# LAN9303_Nucleo144_Shield.net
KiCad netlist of a schematic drawn in EAGLE
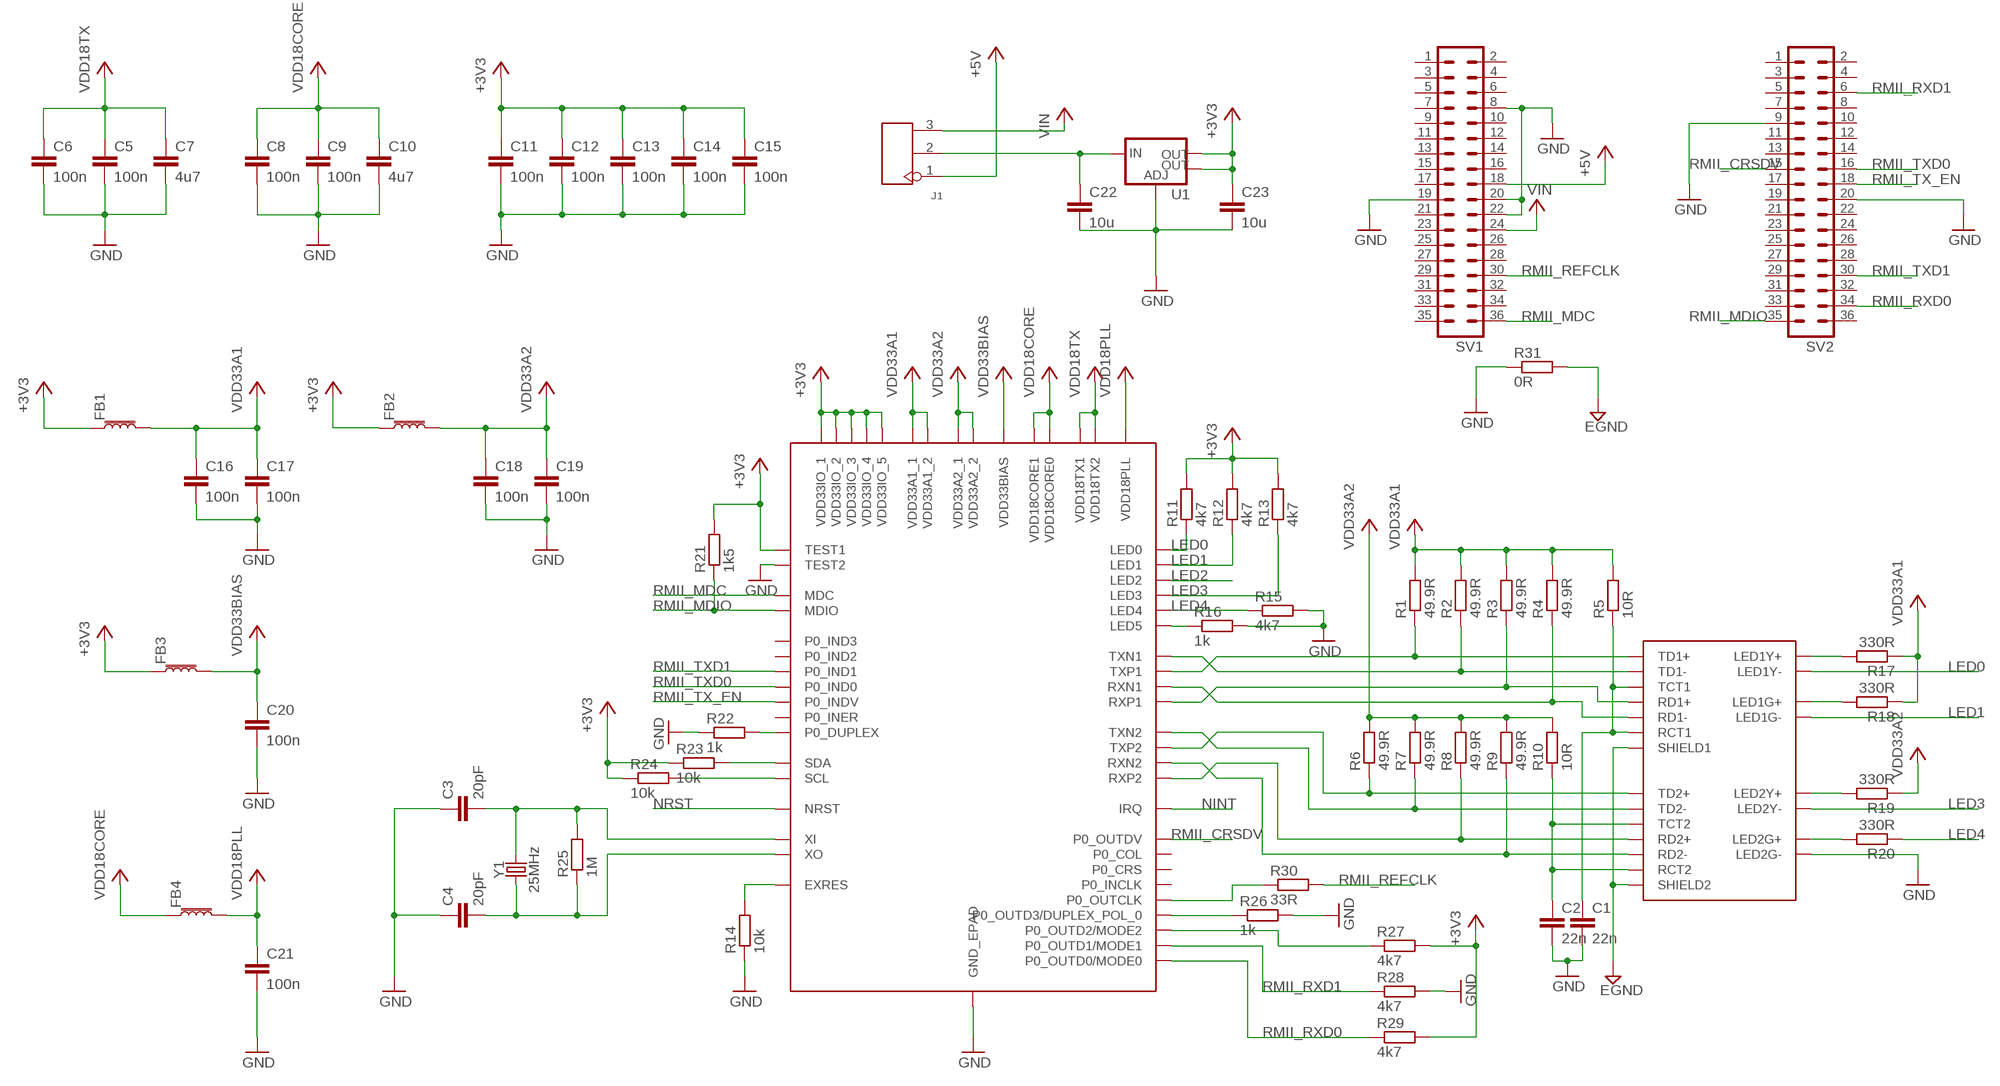
[diagram p0: schematic, sheet 1]

(export (version "E")
  (design (tool "Eeschema 10.0.6"))
  (components
    (comp (ref "C1")
      (value "22n")
      (footprint "eagle-import:C0603")
      (libsource (lib "eagle-import") (part "C-EUC0603"))
    )
    (comp (ref "C2")
      (value "22n")
      (footprint "eagle-import:C0603")
      (libsource (lib "eagle-import") (part "C-EUC0603"))
    )
    (comp (ref "C3")
      (value "20pF")
      (footprint "eagle-import:C0603")
      (libsource (lib "eagle-import") (part "C-EUC0603"))
    )
    (comp (ref "C4")
      (value "20pF")
      (footprint "eagle-import:C0603")
      (libsource (lib "eagle-import") (part "C-EUC0603"))
    )
    (comp (ref "C5")
      (value "100n")
      (footprint "eagle-import:C0603")
      (libsource (lib "eagle-import") (part "C-EUC0603"))
    )
    (comp (ref "C6")
      (value "100n")
      (footprint "eagle-import:C0603")
      (libsource (lib "eagle-import") (part "C-EUC0603"))
    )
    (comp (ref "C7")
      (value "4u7")
      (footprint "eagle-import:C0603")
      (libsource (lib "eagle-import") (part "C-EUC0603"))
    )
    (comp (ref "C8")
      (value "100n")
      (footprint "eagle-import:C0603")
      (libsource (lib "eagle-import") (part "C-EUC0603"))
    )
    (comp (ref "C9")
      (value "100n")
      (footprint "eagle-import:C0603")
      (libsource (lib "eagle-import") (part "C-EUC0603"))
    )
    (comp (ref "C10")
      (value "4u7")
      (footprint "eagle-import:C0603")
      (libsource (lib "eagle-import") (part "C-EUC0603"))
    )
    (comp (ref "C11")
      (value "100n")
      (footprint "eagle-import:C0603")
      (libsource (lib "eagle-import") (part "C-EUC0603"))
    )
    (comp (ref "C12")
      (value "100n")
      (footprint "eagle-import:C0603")
      (libsource (lib "eagle-import") (part "C-EUC0603"))
    )
    (comp (ref "C13")
      (value "100n")
      (footprint "eagle-import:C0603")
      (libsource (lib "eagle-import") (part "C-EUC0603"))
    )
    (comp (ref "C14")
      (value "100n")
      (footprint "eagle-import:C0603")
      (libsource (lib "eagle-import") (part "C-EUC0603"))
    )
    (comp (ref "C15")
      (value "100n")
      (footprint "eagle-import:C0603")
      (libsource (lib "eagle-import") (part "C-EUC0603"))
    )
    (comp (ref "C16")
      (value "100n")
      (footprint "eagle-import:C0603")
      (libsource (lib "eagle-import") (part "C-EUC0603"))
    )
    (comp (ref "C17")
      (value "100n")
      (footprint "eagle-import:C0603")
      (libsource (lib "eagle-import") (part "C-EUC0603"))
    )
    (comp (ref "C18")
      (value "100n")
      (footprint "eagle-import:C0603")
      (libsource (lib "eagle-import") (part "C-EUC0603"))
    )
    (comp (ref "C19")
      (value "100n")
      (footprint "eagle-import:C0603")
      (libsource (lib "eagle-import") (part "C-EUC0603"))
    )
    (comp (ref "C20")
      (value "100n")
      (footprint "eagle-import:C0603")
      (libsource (lib "eagle-import") (part "C-EUC0603"))
    )
    (comp (ref "C21")
      (value "100n")
      (footprint "eagle-import:C0603")
      (libsource (lib "eagle-import") (part "C-EUC0603"))
    )
    (comp (ref "C22")
      (value "10u")
      (footprint "eagle-import:C1206")
      (libsource (lib "eagle-import") (part "C-EUC1206"))
    )
    (comp (ref "C23")
      (value "10u")
      (footprint "eagle-import:C1206")
      (libsource (lib "eagle-import") (part "C-EUC1206"))
    )
    (comp (ref "FB1")
      (value "FERRITE_BEAD-0603")
      (footprint "eagle-import:0603")
      (libsource (lib "eagle-import") (part "FERRITE_BEAD-0603"))
    )
    (comp (ref "FB2")
      (value "FERRITE_BEAD-0603")
      (footprint "eagle-import:0603")
      (libsource (lib "eagle-import") (part "FERRITE_BEAD-0603"))
    )
    (comp (ref "FB3")
      (value "FERRITE_BEAD-0603")
      (footprint "eagle-import:0603")
      (libsource (lib "eagle-import") (part "FERRITE_BEAD-0603"))
    )
    (comp (ref "FB4")
      (value "FERRITE_BEAD-0603")
      (footprint "eagle-import:0603")
      (libsource (lib "eagle-import") (part "FERRITE_BEAD-0603"))
    )
    (comp (ref "J1")
      (value "DIP-BLACK-FEMALE-HEADER-VERT(3P-2.54)")
      (footprint "eagle-import:H3-2.54")
      (fields (field (name "MPN") "F185-1103A0BSYA1"))
      (libsource (lib "eagle-import") (part "DIP-BLACK-FEMALE-HEADER-VERT(3P-2.54)"))
    )
    (comp (ref "R1")
      (value "49.9R")
      (footprint "eagle-import:R0603")
      (libsource (lib "eagle-import") (part "R-EU_R0603"))
    )
    (comp (ref "R2")
      (value "49.9R")
      (footprint "eagle-import:R0603")
      (libsource (lib "eagle-import") (part "R-EU_R0603"))
    )
    (comp (ref "R3")
      (value "49.9R")
      (footprint "eagle-import:R0603")
      (libsource (lib "eagle-import") (part "R-EU_R0603"))
    )
    (comp (ref "R4")
      (value "49.9R")
      (footprint "eagle-import:R0603")
      (libsource (lib "eagle-import") (part "R-EU_R0603"))
    )
    (comp (ref "R5")
      (value "10R")
      (footprint "eagle-import:R0603")
      (libsource (lib "eagle-import") (part "R-EU_R0603"))
    )
    (comp (ref "R6")
      (value "49.9R")
      (footprint "eagle-import:R0603")
      (libsource (lib "eagle-import") (part "R-EU_R0603"))
    )
    (comp (ref "R7")
      (value "49.9R")
      (footprint "eagle-import:R0603")
      (libsource (lib "eagle-import") (part "R-EU_R0603"))
    )
    (comp (ref "R8")
      (value "49.9R")
      (footprint "eagle-import:R0603")
      (libsource (lib "eagle-import") (part "R-EU_R0603"))
    )
    (comp (ref "R9")
      (value "49.9R")
      (footprint "eagle-import:R0603")
      (libsource (lib "eagle-import") (part "R-EU_R0603"))
    )
    (comp (ref "R10")
      (value "10R")
      (footprint "eagle-import:R0603")
      (libsource (lib "eagle-import") (part "R-EU_R0603"))
    )
    (comp (ref "R11")
      (value "4k7")
      (footprint "eagle-import:R0603")
      (libsource (lib "eagle-import") (part "R-EU_R0603"))
    )
    (comp (ref "R12")
      (value "4k7")
      (footprint "eagle-import:R0603")
      (libsource (lib "eagle-import") (part "R-EU_R0603"))
    )
    (comp (ref "R13")
      (value "4k7")
      (footprint "eagle-import:R0603")
      (libsource (lib "eagle-import") (part "R-EU_R0603"))
    )
    (comp (ref "R14")
      (value "10k")
      (footprint "eagle-import:R0603")
      (libsource (lib "eagle-import") (part "R-EU_R0603"))
    )
    (comp (ref "R15")
      (value "4k7")
      (footprint "eagle-import:R0603")
      (libsource (lib "eagle-import") (part "R-EU_R0603"))
    )
    (comp (ref "R16")
      (value "1k")
      (footprint "eagle-import:R0603")
      (libsource (lib "eagle-import") (part "R-EU_R0603"))
    )
    (comp (ref "R17")
      (value "330R")
      (footprint "eagle-import:R0603")
      (libsource (lib "eagle-import") (part "R-EU_R0603"))
    )
    (comp (ref "R18")
      (value "330R")
      (footprint "eagle-import:R0603")
      (libsource (lib "eagle-import") (part "R-EU_R0603"))
    )
    (comp (ref "R19")
      (value "330R")
      (footprint "eagle-import:R0603")
      (libsource (lib "eagle-import") (part "R-EU_R0603"))
    )
    (comp (ref "R20")
      (value "330R")
      (footprint "eagle-import:R0603")
      (libsource (lib "eagle-import") (part "R-EU_R0603"))
    )
    (comp (ref "R21")
      (value "1k5")
      (footprint "eagle-import:R0603")
      (libsource (lib "eagle-import") (part "R-EU_R0603"))
    )
    (comp (ref "R22")
      (value "1k")
      (footprint "eagle-import:R0603")
      (libsource (lib "eagle-import") (part "R-EU_R0603"))
    )
    (comp (ref "R23")
      (value "10k")
      (footprint "eagle-import:R0603")
      (libsource (lib "eagle-import") (part "R-EU_R0603"))
    )
    (comp (ref "R24")
      (value "10k")
      (footprint "eagle-import:R0603")
      (libsource (lib "eagle-import") (part "R-EU_R0603"))
    )
    (comp (ref "R25")
      (value "1M")
      (footprint "eagle-import:R0603")
      (libsource (lib "eagle-import") (part "R-EU_R0603"))
    )
    (comp (ref "R26")
      (value "1k")
      (footprint "eagle-import:R0603")
      (libsource (lib "eagle-import") (part "R-EU_R0603"))
    )
    (comp (ref "R27")
      (value "4k7")
      (footprint "eagle-import:R0603")
      (libsource (lib "eagle-import") (part "R-EU_R0603"))
    )
    (comp (ref "R28")
      (value "4k7")
      (footprint "eagle-import:R0603")
      (libsource (lib "eagle-import") (part "R-EU_R0603"))
    )
    (comp (ref "R29")
      (value "4k7")
      (footprint "eagle-import:R0603")
      (libsource (lib "eagle-import") (part "R-EU_R0603"))
    )
    (comp (ref "R30")
      (value "33R")
      (footprint "eagle-import:R0603")
      (libsource (lib "eagle-import") (part "R-EU_R0603"))
    )
    (comp (ref "R31")
      (value "0R")
      (footprint "eagle-import:R0805")
      (libsource (lib "eagle-import") (part "R-EU_R0805"))
    )
    (comp (ref "SV1")
      (value "MA18-2")
      (footprint "eagle-import:MA18-2")
      (libsource (lib "eagle-import") (part "MA18-2"))
    )
    (comp (ref "SV2")
      (value "MA18-2")
      (footprint "eagle-import:MA18-2")
      (libsource (lib "eagle-import") (part "MA18-2"))
    )
    (comp (ref "U$1")
      (value "LAN9303")
      (footprint "eagle-import:QFN56")
      (libsource (lib "eagle-import") (part "LAN9303_ABZJ"))
    )
    (comp (ref "U$2")
      (value "WE_DUAL_RJ45JACK")
      (footprint "eagle-import:DUAL_RJ45")
      (libsource (lib "eagle-import") (part "WE_DUAL_RJ45JACK"))
    )
    (comp (ref "U1")
      (value "V_REG_LM1117SOT223")
      (footprint "eagle-import:SOT223")
      (libsource (lib "eagle-import") (part "V_REG_LM1117SOT223"))
    )
    (comp (ref "Y1")
      (value "25MHz")
      (footprint "eagle-import:CRYSTAL-SMD-5X3.2-2PAD")
      (libsource (lib "eagle-import") (part "CRYSTALSMD-5X3.2-2PAD"))
    )
  )
  (nets
    (net (code "1") (name "+3V3") (class "Default")
      (node (ref "C11") (pin "1") (pinfunction "1_1") (pintype "passive"))
      (node (ref "C12") (pin "1") (pinfunction "1_1") (pintype "passive"))
      (node (ref "C13") (pin "1") (pinfunction "1_1") (pintype "passive"))
      (node (ref "C14") (pin "1") (pinfunction "1_1") (pintype "passive"))
      (node (ref "C15") (pin "1") (pinfunction "1_1") (pintype "passive"))
      (node (ref "C23") (pin "1") (pinfunction "1_1") (pintype "passive"))
      (node (ref "FB1") (pin "1") (pinfunction "1_1") (pintype "passive"))
      (node (ref "FB2") (pin "1") (pinfunction "1_1") (pintype "passive"))
      (node (ref "FB3") (pin "1") (pinfunction "1_1") (pintype "passive"))
      (node (ref "R11") (pin "2") (pinfunction "2_2") (pintype "passive"))
      (node (ref "R12") (pin "2") (pinfunction "2_2") (pintype "passive"))
      (node (ref "R13") (pin "2") (pinfunction "2_2") (pintype "passive"))
      (node (ref "R21") (pin "2") (pinfunction "2_2") (pintype "passive"))
      (node (ref "R23") (pin "1") (pinfunction "1_1") (pintype "passive"))
      (node (ref "R24") (pin "1") (pinfunction "1_1") (pintype "passive"))
      (node (ref "R27") (pin "2") (pinfunction "2_2") (pintype "passive"))
      (node (ref "R29") (pin "2") (pinfunction "2_2") (pintype "passive"))
      (node (ref "U$1") (pin "15") (pinfunction "VDD33IO_2_15") (pintype "bidirectional"))
      (node (ref "U$1") (pin "23") (pinfunction "VDD33IO_3_23") (pintype "bidirectional"))
      (node (ref "U$1") (pin "30") (pinfunction "VDD33IO_4_30") (pintype "bidirectional"))
      (node (ref "U$1") (pin "32") (pinfunction "VDD33IO_5_32") (pintype "bidirectional"))
      (node (ref "U$1") (pin "33") (pinfunction "TEST1_33") (pintype "bidirectional"))
      (node (ref "U$1") (pin "9") (pinfunction "VDD33IO_1_9") (pintype "bidirectional"))
      (node (ref "U1") (pin "2") (pinfunction "OUT_2") (pintype "output"))
      (node (ref "U1") (pin "4") (pinfunction "OUT_4") (pintype "output"))
    )
    (net (code "2") (name "+5V") (class "Default")
      (node (ref "J1") (pin "1") (pinfunction "P$1_1") (pintype "bidirectional"))
      (node (ref "SV1") (pin "18") (pinfunction "18_18") (pintype "passive"))
    )
    (net (code "3") (name "/LED0") (class "Default")
      (node (ref "R11") (pin "1") (pinfunction "1_1") (pintype "passive"))
      (node (ref "U$1") (pin "29") (pinfunction "LED0_29") (pintype "bidirectional"))
      (node (ref "U$2") (pin "P$1_10") (pinfunction "LED1Y-_P$1_10") (pintype "bidirectional"))
    )
    (net (code "4") (name "/LED1") (class "Default")
      (node (ref "R12") (pin "1") (pinfunction "1_1") (pintype "passive"))
      (node (ref "U$1") (pin "28") (pinfunction "LED1_28") (pintype "bidirectional"))
      (node (ref "U$2") (pin "P$1_12") (pinfunction "LED1G-_P$1_12") (pintype "bidirectional"))
    )
    (net (code "5") (name "/LED2") (class "Default")
      (node (ref "U$1") (pin "27") (pinfunction "LED2_27") (pintype "bidirectional"))
    )
    (net (code "6") (name "/LED3") (class "Default")
      (node (ref "R13") (pin "1") (pinfunction "1_1") (pintype "passive"))
      (node (ref "U$1") (pin "26") (pinfunction "LED3_26") (pintype "bidirectional"))
      (node (ref "U$2") (pin "P$2_10") (pinfunction "LED2Y-_P$2_10") (pintype "bidirectional"))
    )
    (net (code "7") (name "/LED4") (class "Default")
      (node (ref "R15") (pin "1") (pinfunction "1_1") (pintype "passive"))
      (node (ref "R20") (pin "1") (pinfunction "1_1") (pintype "passive"))
      (node (ref "U$1") (pin "25") (pinfunction "LED4_25") (pintype "bidirectional"))
    )
    (net (code "8") (name "/NINT") (class "Default")
      (node (ref "U$1") (pin "38") (pinfunction "IRQ_38") (pintype "bidirectional"))
    )
    (net (code "9") (name "/NRST") (class "Default")
      (node (ref "U$1") (pin "37") (pinfunction "NRST_37") (pintype "bidirectional"))
    )
    (net (code "10") (name "/RMII_CRSDV") (class "Default")
      (node (ref "SV2") (pin "15") (pinfunction "15_15") (pintype "passive"))
      (node (ref "U$1") (pin "16") (pinfunction "P0_OUTDV_16") (pintype "bidirectional"))
    )
    (net (code "11") (name "/RMII_MDC") (class "Default")
      (node (ref "SV1") (pin "36") (pinfunction "36_36") (pintype "passive"))
      (node (ref "U$1") (pin "22") (pinfunction "MDC_22") (pintype "bidirectional"))
    )
    (net (code "12") (name "/RMII_MDIO") (class "Default")
      (node (ref "R21") (pin "1") (pinfunction "1_1") (pintype "passive"))
      (node (ref "SV2") (pin "35") (pinfunction "35_35") (pintype "passive"))
      (node (ref "U$1") (pin "21") (pinfunction "MDIO_21") (pintype "bidirectional"))
    )
    (net (code "13") (name "/RMII_REFCLK") (class "Default")
      (node (ref "R30") (pin "2") (pinfunction "2_2") (pintype "passive"))
      (node (ref "SV1") (pin "30") (pinfunction "30_30") (pintype "passive"))
    )
    (net (code "14") (name "/RMII_RXD0") (class "Default")
      (node (ref "R29") (pin "1") (pinfunction "1_1") (pintype "passive"))
      (node (ref "SV2") (pin "34") (pinfunction "34_34") (pintype "passive"))
      (node (ref "U$1") (pin "14") (pinfunction "P0_OUTD0/MODE0_14") (pintype "bidirectional"))
    )
    (net (code "15") (name "/RMII_RXD1") (class "Default")
      (node (ref "R28") (pin "1") (pinfunction "1_1") (pintype "passive"))
      (node (ref "SV2") (pin "6") (pinfunction "6_6") (pintype "passive"))
      (node (ref "U$1") (pin "13") (pinfunction "P0_OUTD1/MODE1_13") (pintype "bidirectional"))
    )
    (net (code "16") (name "/RMII_TXD0") (class "Default")
      (node (ref "SV2") (pin "16") (pinfunction "16_16") (pintype "passive"))
      (node (ref "U$1") (pin "5") (pinfunction "P0_IND0_5") (pintype "bidirectional"))
    )
    (net (code "17") (name "/RMII_TXD1") (class "Default")
      (node (ref "SV2") (pin "30") (pinfunction "30_30") (pintype "passive"))
      (node (ref "U$1") (pin "4") (pinfunction "P0_IND1_4") (pintype "bidirectional"))
    )
    (net (code "18") (name "/RMII_TX_EN") (class "Default")
      (node (ref "SV2") (pin "18") (pinfunction "18_18") (pintype "passive"))
      (node (ref "U$1") (pin "6") (pinfunction "P0_INDV_6") (pintype "bidirectional"))
    )
    (net (code "19") (name "EGND") (class "Default")
      (node (ref "R31") (pin "2") (pinfunction "2_2") (pintype "passive"))
      (node (ref "U$2") (pin "P$1_8") (pinfunction "SHIELD1_P$1_8") (pintype "bidirectional"))
      (node (ref "U$2") (pin "P$2_8") (pinfunction "SHIELD2_P$2_8") (pintype "bidirectional"))
    )
    (net (code "20") (name "GND") (class "Default")
      (node (ref "C1") (pin "2") (pinfunction "2_2") (pintype "passive"))
      (node (ref "C10") (pin "2") (pinfunction "2_2") (pintype "passive"))
      (node (ref "C11") (pin "2") (pinfunction "2_2") (pintype "passive"))
      (node (ref "C12") (pin "2") (pinfunction "2_2") (pintype "passive"))
      (node (ref "C13") (pin "2") (pinfunction "2_2") (pintype "passive"))
      (node (ref "C14") (pin "2") (pinfunction "2_2") (pintype "passive"))
      (node (ref "C15") (pin "2") (pinfunction "2_2") (pintype "passive"))
      (node (ref "C16") (pin "2") (pinfunction "2_2") (pintype "passive"))
      (node (ref "C17") (pin "2") (pinfunction "2_2") (pintype "passive"))
      (node (ref "C18") (pin "2") (pinfunction "2_2") (pintype "passive"))
      (node (ref "C19") (pin "2") (pinfunction "2_2") (pintype "passive"))
      (node (ref "C2") (pin "2") (pinfunction "2_2") (pintype "passive"))
      (node (ref "C20") (pin "2") (pinfunction "2_2") (pintype "passive"))
      (node (ref "C21") (pin "2") (pinfunction "2_2") (pintype "passive"))
      (node (ref "C22") (pin "2") (pinfunction "2_2") (pintype "passive"))
      (node (ref "C23") (pin "2") (pinfunction "2_2") (pintype "passive"))
      (node (ref "C3") (pin "1") (pinfunction "1_1") (pintype "passive"))
      (node (ref "C4") (pin "1") (pinfunction "1_1") (pintype "passive"))
      (node (ref "C5") (pin "2") (pinfunction "2_2") (pintype "passive"))
      (node (ref "C6") (pin "2") (pinfunction "2_2") (pintype "passive"))
      (node (ref "C7") (pin "2") (pinfunction "2_2") (pintype "passive"))
      (node (ref "C8") (pin "2") (pinfunction "2_2") (pintype "passive"))
      (node (ref "C9") (pin "2") (pinfunction "2_2") (pintype "passive"))
      (node (ref "R14") (pin "1") (pinfunction "1_1") (pintype "passive"))
      (node (ref "R15") (pin "2") (pinfunction "2_2") (pintype "passive"))
      (node (ref "R16") (pin "2") (pinfunction "2_2") (pintype "passive"))
      (node (ref "R22") (pin "1") (pinfunction "1_1") (pintype "passive"))
      (node (ref "R26") (pin "2") (pinfunction "2_2") (pintype "passive"))
      (node (ref "R28") (pin "2") (pinfunction "2_2") (pintype "passive"))
      (node (ref "R31") (pin "1") (pinfunction "1_1") (pintype "passive"))
      (node (ref "SV1") (pin "19") (pinfunction "19_19") (pintype "passive"))
      (node (ref "SV1") (pin "20") (pinfunction "20_20") (pintype "passive"))
      (node (ref "SV1") (pin "22") (pinfunction "22_22") (pintype "passive"))
      (node (ref "SV1") (pin "8") (pinfunction "8_8") (pintype "passive"))
      (node (ref "SV2") (pin "20") (pinfunction "20_20") (pintype "passive"))
      (node (ref "SV2") (pin "9") (pinfunction "9_9") (pintype "passive"))
      (node (ref "U$1") (pin "34") (pinfunction "TEST2_34") (pintype "bidirectional"))
      (node (ref "U$1") (pin "EPAD") (pinfunction "GND_EPAD_EPAD") (pintype "bidirectional"))
      (node (ref "U$2") (pin "P$2_12") (pinfunction "LED2G-_P$2_12") (pintype "bidirectional"))
      (node (ref "U1") (pin "1") (pinfunction "ADJ_1") (pintype "input"))
    )
    (net (code "21") (name "Net-(J1-P$2)") (class "Default")
      (node (ref "C22") (pin "1") (pinfunction "1_1") (pintype "passive"))
      (node (ref "J1") (pin "2") (pinfunction "P$2_2") (pintype "bidirectional"))
      (node (ref "U1") (pin "3") (pinfunction "IN_3") (pintype "input"))
    )
    (net (code "22") (name "Net-(U$1-EXRES)") (class "Default")
      (node (ref "R14") (pin "2") (pinfunction "2_2") (pintype "passive"))
      (node (ref "U$1") (pin "49") (pinfunction "EXRES_49") (pintype "bidirectional"))
    )
    (net (code "23") (name "Net-(U$1-LED5)") (class "Default")
      (node (ref "R16") (pin "1") (pinfunction "1_1") (pintype "passive"))
      (node (ref "U$1") (pin "24") (pinfunction "LED5_24") (pintype "bidirectional"))
    )
    (net (code "24") (name "Net-(U$1-P0_DUPLEX)") (class "Default")
      (node (ref "R22") (pin "2") (pinfunction "2_2") (pintype "passive"))
      (node (ref "U$1") (pin "20") (pinfunction "P0_DUPLEX_20") (pintype "bidirectional"))
    )
    (net (code "25") (name "Net-(U$1-P0_OUTCLK)") (class "Default")
      (node (ref "R30") (pin "1") (pinfunction "1_1") (pintype "passive"))
      (node (ref "U$1") (pin "17") (pinfunction "P0_OUTCLK_17") (pintype "bidirectional"))
    )
    (net (code "26") (name "Net-(U$1-P0_OUTD2{slash}MODE2)") (class "Default")
      (node (ref "R27") (pin "1") (pinfunction "1_1") (pintype "passive"))
      (node (ref "U$1") (pin "12") (pinfunction "P0_OUTD2/MODE2_12") (pintype "bidirectional"))
    )
    (net (code "27") (name "Net-(U$1-P0_OUTD3{slash}DUPLEX_POL_0)") (class "Default")
      (node (ref "R26") (pin "1") (pinfunction "1_1") (pintype "passive"))
      (node (ref "U$1") (pin "11") (pinfunction "P0_OUTD3/DUPLEX_POL_0_11") (pintype "bidirectional"))
    )
    (net (code "28") (name "Net-(U$1-RXN1)") (class "Default")
      (node (ref "R4") (pin "1") (pinfunction "1_1") (pintype "passive"))
      (node (ref "U$1") (pin "45") (pinfunction "RXN1_45") (pintype "bidirectional"))
      (node (ref "U$2") (pin "P$1_6") (pinfunction "RD1-_P$1_6") (pintype "bidirectional"))
    )
    (net (code "29") (name "Net-(U$1-RXN2)") (class "Default")
      (node (ref "R9") (pin "1") (pinfunction "1_1") (pintype "passive"))
      (node (ref "U$1") (pin "54") (pinfunction "RXN2_54") (pintype "bidirectional"))
      (node (ref "U$2") (pin "P$2_6") (pinfunction "RD2-_P$2_6") (pintype "bidirectional"))
    )
    (net (code "30") (name "Net-(U$1-RXP1)") (class "Default")
      (node (ref "R3") (pin "1") (pinfunction "1_1") (pintype "passive"))
      (node (ref "U$1") (pin "46") (pinfunction "RXP1_46") (pintype "bidirectional"))
      (node (ref "U$2") (pin "P$1_3") (pinfunction "RD1+_P$1_3") (pintype "bidirectional"))
    )
    (net (code "31") (name "Net-(U$1-RXP2)") (class "Default")
      (node (ref "R8") (pin "1") (pinfunction "1_1") (pintype "passive"))
      (node (ref "U$1") (pin "53") (pinfunction "RXP2_53") (pintype "bidirectional"))
      (node (ref "U$2") (pin "P$2_3") (pinfunction "RD2+_P$2_3") (pintype "bidirectional"))
    )
    (net (code "32") (name "Net-(U$1-SCL)") (class "Default")
      (node (ref "R24") (pin "2") (pinfunction "2_2") (pintype "passive"))
      (node (ref "U$1") (pin "36") (pinfunction "SCL_36") (pintype "bidirectional"))
    )
    (net (code "33") (name "Net-(U$1-SDA)") (class "Default")
      (node (ref "R23") (pin "2") (pinfunction "2_2") (pintype "passive"))
      (node (ref "U$1") (pin "35") (pinfunction "SDA_35") (pintype "bidirectional"))
    )
    (net (code "34") (name "Net-(U$1-TXN1)") (class "Default")
      (node (ref "R2") (pin "1") (pinfunction "1_1") (pintype "passive"))
      (node (ref "U$1") (pin "42") (pinfunction "TXN1_42") (pintype "bidirectional"))
      (node (ref "U$2") (pin "P$1_2") (pinfunction "TD1-_P$1_2") (pintype "bidirectional"))
    )
    (net (code "35") (name "Net-(U$1-TXN2)") (class "Default")
      (node (ref "R7") (pin "1") (pinfunction "1_1") (pintype "passive"))
      (node (ref "U$1") (pin "1") (pinfunction "TXN2_1") (pintype "bidirectional"))
      (node (ref "U$2") (pin "P$2_2") (pinfunction "TD2-_P$2_2") (pintype "bidirectional"))
    )
    (net (code "36") (name "Net-(U$1-TXP1)") (class "Default")
      (node (ref "R1") (pin "1") (pinfunction "1_1") (pintype "passive"))
      (node (ref "U$1") (pin "43") (pinfunction "TXP1_43") (pintype "bidirectional"))
      (node (ref "U$2") (pin "P$1_1") (pinfunction "TD1+_P$1_1") (pintype "bidirectional"))
    )
    (net (code "37") (name "Net-(U$1-TXP2)") (class "Default")
      (node (ref "R6") (pin "1") (pinfunction "1_1") (pintype "passive"))
      (node (ref "U$1") (pin "56") (pinfunction "TXP2_56") (pintype "bidirectional"))
      (node (ref "U$2") (pin "P$2_1") (pinfunction "TD2+_P$2_1") (pintype "bidirectional"))
    )
    (net (code "38") (name "Net-(U$1-XI)") (class "Default")
      (node (ref "C3") (pin "2") (pinfunction "2_2") (pintype "passive"))
      (node (ref "R25") (pin "2") (pinfunction "2_2") (pintype "passive"))
      (node (ref "U$1") (pin "39") (pinfunction "XI_39") (pintype "bidirectional"))
      (node (ref "Y1") (pin "P$2") (pinfunction "2_P$2") (pintype "passive"))
    )
    (net (code "39") (name "Net-(U$1-XO)") (class "Default")
      (node (ref "C4") (pin "2") (pinfunction "2_2") (pintype "passive"))
      (node (ref "R25") (pin "1") (pinfunction "1_1") (pintype "passive"))
      (node (ref "U$1") (pin "40") (pinfunction "XO_40") (pintype "bidirectional"))
      (node (ref "Y1") (pin "P$1") (pinfunction "1_P$1") (pintype "passive"))
    )
    (net (code "40") (name "Net-(U$2-LED1G+)") (class "Default")
      (node (ref "R18") (pin "2") (pinfunction "2_2") (pintype "passive"))
      (node (ref "U$2") (pin "P$1_11") (pinfunction "LED1G+_P$1_11") (pintype "bidirectional"))
    )
    (net (code "41") (name "Net-(U$2-LED1Y+)") (class "Default")
      (node (ref "R17") (pin "2") (pinfunction "2_2") (pintype "passive"))
      (node (ref "U$2") (pin "P$1_9") (pinfunction "LED1Y+_P$1_9") (pintype "bidirectional"))
    )
    (net (code "42") (name "Net-(U$2-LED2G+)") (class "Default")
      (node (ref "R20") (pin "2") (pinfunction "2_2") (pintype "passive"))
      (node (ref "U$2") (pin "P$2_11") (pinfunction "LED2G+_P$2_11") (pintype "bidirectional"))
    )
    (net (code "43") (name "Net-(U$2-LED2Y+)") (class "Default")
      (node (ref "R19") (pin "2") (pinfunction "2_2") (pintype "passive"))
      (node (ref "U$2") (pin "P$2_9") (pinfunction "LED2Y+_P$2_9") (pintype "bidirectional"))
    )
    (net (code "44") (name "Net-(U$2-RCT1)") (class "Default")
      (node (ref "C1") (pin "1") (pinfunction "1_1") (pintype "passive"))
      (node (ref "R5") (pin "1") (pinfunction "1_1") (pintype "passive"))
      (node (ref "U$2") (pin "P$1_4") (pinfunction "TCT1_P$1_4") (pintype "bidirectional"))
      (node (ref "U$2") (pin "P$1_5") (pinfunction "RCT1_P$1_5") (pintype "bidirectional"))
    )
    (net (code "45") (name "Net-(U$2-RCT2)") (class "Default")
      (node (ref "C2") (pin "1") (pinfunction "1_1") (pintype "passive"))
      (node (ref "R10") (pin "1") (pinfunction "1_1") (pintype "passive"))
      (node (ref "U$2") (pin "P$2_4") (pinfunction "TCT2_P$2_4") (pintype "bidirectional"))
      (node (ref "U$2") (pin "P$2_5") (pinfunction "RCT2_P$2_5") (pintype "bidirectional"))
    )
    (net (code "46") (name "VDD18CORE") (class "Default")
      (node (ref "C10") (pin "1") (pinfunction "1_1") (pintype "passive"))
      (node (ref "C8") (pin "1") (pinfunction "1_1") (pintype "passive"))
      (node (ref "C9") (pin "1") (pinfunction "1_1") (pintype "passive"))
      (node (ref "FB4") (pin "1") (pinfunction "1_1") (pintype "passive"))
      (node (ref "U$1") (pin "10") (pinfunction "VDD18CORE0_10") (pintype "bidirectional"))
      (node (ref "U$1") (pin "31") (pinfunction "VDD18CORE1_31") (pintype "bidirectional"))
    )
    (net (code "47") (name "VDD18PLL") (class "Default")
      (node (ref "C21") (pin "1") (pinfunction "1_1") (pintype "passive"))
      (node (ref "FB4") (pin "2") (pinfunction "2_2") (pintype "passive"))
      (node (ref "U$1") (pin "41") (pinfunction "VDD18PLL_41") (pintype "bidirectional"))
    )
    (net (code "48") (name "VDD18TX") (class "Default")
      (node (ref "C5") (pin "1") (pinfunction "1_1") (pintype "passive"))
      (node (ref "C6") (pin "1") (pinfunction "1_1") (pintype "passive"))
      (node (ref "C7") (pin "1") (pinfunction "1_1") (pintype "passive"))
      (node (ref "U$1") (pin "48") (pinfunction "VDD18TX1_48") (pintype "bidirectional"))
      (node (ref "U$1") (pin "51") (pinfunction "VDD18TX2_51") (pintype "bidirectional"))
    )
    (net (code "49") (name "VDD33A1") (class "Default")
      (node (ref "C16") (pin "1") (pinfunction "1_1") (pintype "passive"))
      (node (ref "C17") (pin "1") (pinfunction "1_1") (pintype "passive"))
      (node (ref "FB1") (pin "2") (pinfunction "2_2") (pintype "passive"))
      (node (ref "R1") (pin "2") (pinfunction "2_2") (pintype "passive"))
      (node (ref "R17") (pin "1") (pinfunction "1_1") (pintype "passive"))
      (node (ref "R18") (pin "1") (pinfunction "1_1") (pintype "passive"))
      (node (ref "R2") (pin "2") (pinfunction "2_2") (pintype "passive"))
      (node (ref "R3") (pin "2") (pinfunction "2_2") (pintype "passive"))
      (node (ref "R4") (pin "2") (pinfunction "2_2") (pintype "passive"))
      (node (ref "R5") (pin "2") (pinfunction "2_2") (pintype "passive"))
      (node (ref "U$1") (pin "44") (pinfunction "VDD33A1_1_44") (pintype "bidirectional"))
      (node (ref "U$1") (pin "47") (pinfunction "VDD33A1_2_47") (pintype "bidirectional"))
    )
    (net (code "50") (name "VDD33A2") (class "Default")
      (node (ref "C18") (pin "1") (pinfunction "1_1") (pintype "passive"))
      (node (ref "C19") (pin "1") (pinfunction "1_1") (pintype "passive"))
      (node (ref "FB2") (pin "2") (pinfunction "2_2") (pintype "passive"))
      (node (ref "R10") (pin "2") (pinfunction "2_2") (pintype "passive"))
      (node (ref "R19") (pin "1") (pinfunction "1_1") (pintype "passive"))
      (node (ref "R6") (pin "2") (pinfunction "2_2") (pintype "passive"))
      (node (ref "R7") (pin "2") (pinfunction "2_2") (pintype "passive"))
      (node (ref "R8") (pin "2") (pinfunction "2_2") (pintype "passive"))
      (node (ref "R9") (pin "2") (pinfunction "2_2") (pintype "passive"))
      (node (ref "U$1") (pin "52") (pinfunction "VDD33A2_1_52") (pintype "bidirectional"))
      (node (ref "U$1") (pin "55") (pinfunction "VDD33A2_2_55") (pintype "bidirectional"))
    )
    (net (code "51") (name "VDD33BIAS") (class "Default")
      (node (ref "C20") (pin "1") (pinfunction "1_1") (pintype "passive"))
      (node (ref "FB3") (pin "2") (pinfunction "2_2") (pintype "passive"))
      (node (ref "U$1") (pin "50") (pinfunction "VDD33BIAS_50") (pintype "bidirectional"))
    )
    (net (code "52") (name "VIN") (class "Default")
      (node (ref "J1") (pin "3") (pinfunction "P$3_3") (pintype "bidirectional"))
      (node (ref "SV1") (pin "24") (pinfunction "24_24") (pintype "passive"))
    )
    (net (code "53") (name "unconnected-(SV1-Pad1)") (class "Default")
      (node (ref "SV1") (pin "1") (pinfunction "1_1") (pintype "passive"))
    )
    (net (code "54") (name "unconnected-(SV1-Pad2)") (class "Default")
      (node (ref "SV1") (pin "2") (pinfunction "2_2") (pintype "passive"))
    )
    (net (code "55") (name "unconnected-(SV1-Pad3)") (class "Default")
      (node (ref "SV1") (pin "3") (pinfunction "3_3") (pintype "passive"))
    )
    (net (code "56") (name "unconnected-(SV1-Pad4)") (class "Default")
      (node (ref "SV1") (pin "4") (pinfunction "4_4") (pintype "passive"))
    )
    (net (code "57") (name "unconnected-(SV1-Pad5)") (class "Default")
      (node (ref "SV1") (pin "5") (pinfunction "5_5") (pintype "passive"))
    )
    (net (code "58") (name "unconnected-(SV1-Pad6)") (class "Default")
      (node (ref "SV1") (pin "6") (pinfunction "6_6") (pintype "passive"))
    )
    (net (code "59") (name "unconnected-(SV1-Pad7)") (class "Default")
      (node (ref "SV1") (pin "7") (pinfunction "7_7") (pintype "passive"))
    )
    (net (code "60") (name "unconnected-(SV1-Pad9)") (class "Default")
      (node (ref "SV1") (pin "9") (pinfunction "9_9") (pintype "passive"))
    )
    (net (code "61") (name "unconnected-(SV1-Pad10)") (class "Default")
      (node (ref "SV1") (pin "10") (pinfunction "10_10") (pintype "passive"))
    )
    (net (code "62") (name "unconnected-(SV1-Pad11)") (class "Default")
      (node (ref "SV1") (pin "11") (pinfunction "11_11") (pintype "passive"))
    )
    (net (code "63") (name "unconnected-(SV1-Pad12)") (class "Default")
      (node (ref "SV1") (pin "12") (pinfunction "12_12") (pintype "passive"))
    )
    (net (code "64") (name "unconnected-(SV1-Pad13)") (class "Default")
      (node (ref "SV1") (pin "13") (pinfunction "13_13") (pintype "passive"))
    )
    (net (code "65") (name "unconnected-(SV1-Pad14)") (class "Default")
      (node (ref "SV1") (pin "14") (pinfunction "14_14") (pintype "passive"))
    )
    (net (code "66") (name "unconnected-(SV1-Pad15)") (class "Default")
      (node (ref "SV1") (pin "15") (pinfunction "15_15") (pintype "passive"))
    )
    (net (code "67") (name "unconnected-(SV1-Pad16)") (class "Default")
      (node (ref "SV1") (pin "16") (pinfunction "16_16") (pintype "passive"))
    )
    (net (code "68") (name "unconnected-(SV1-Pad17)") (class "Default")
      (node (ref "SV1") (pin "17") (pinfunction "17_17") (pintype "passive"))
    )
    (net (code "69") (name "unconnected-(SV1-Pad21)") (class "Default")
      (node (ref "SV1") (pin "21") (pinfunction "21_21") (pintype "passive"))
    )
    (net (code "70") (name "unconnected-(SV1-Pad23)") (class "Default")
      (node (ref "SV1") (pin "23") (pinfunction "23_23") (pintype "passive"))
    )
    (net (code "71") (name "unconnected-(SV1-Pad25)") (class "Default")
      (node (ref "SV1") (pin "25") (pinfunction "25_25") (pintype "passive"))
    )
    (net (code "72") (name "unconnected-(SV1-Pad26)") (class "Default")
      (node (ref "SV1") (pin "26") (pinfunction "26_26") (pintype "passive"))
    )
    (net (code "73") (name "unconnected-(SV1-Pad27)") (class "Default")
      (node (ref "SV1") (pin "27") (pinfunction "27_27") (pintype "passive"))
    )
    (net (code "74") (name "unconnected-(SV1-Pad28)") (class "Default")
      (node (ref "SV1") (pin "28") (pinfunction "28_28") (pintype "passive"))
    )
    (net (code "75") (name "unconnected-(SV1-Pad29)") (class "Default")
      (node (ref "SV1") (pin "29") (pinfunction "29_29") (pintype "passive"))
    )
    (net (code "76") (name "unconnected-(SV1-Pad31)") (class "Default")
      (node (ref "SV1") (pin "31") (pinfunction "31_31") (pintype "passive"))
    )
    (net (code "77") (name "unconnected-(SV1-Pad32)") (class "Default")
      (node (ref "SV1") (pin "32") (pinfunction "32_32") (pintype "passive"))
    )
    (net (code "78") (name "unconnected-(SV1-Pad33)") (class "Default")
      (node (ref "SV1") (pin "33") (pinfunction "33_33") (pintype "passive"))
    )
    (net (code "79") (name "unconnected-(SV1-Pad34)") (class "Default")
      (node (ref "SV1") (pin "34") (pinfunction "34_34") (pintype "passive"))
    )
    (net (code "80") (name "unconnected-(SV1-Pad35)") (class "Default")
      (node (ref "SV1") (pin "35") (pinfunction "35_35") (pintype "passive"))
    )
    (net (code "81") (name "unconnected-(SV2-Pad1)") (class "Default")
      (node (ref "SV2") (pin "1") (pinfunction "1_1") (pintype "passive"))
    )
    (net (code "82") (name "unconnected-(SV2-Pad2)") (class "Default")
      (node (ref "SV2") (pin "2") (pinfunction "2_2") (pintype "passive"))
    )
    (net (code "83") (name "unconnected-(SV2-Pad3)") (class "Default")
      (node (ref "SV2") (pin "3") (pinfunction "3_3") (pintype "passive"))
    )
    (net (code "84") (name "unconnected-(SV2-Pad4)") (class "Default")
      (node (ref "SV2") (pin "4") (pinfunction "4_4") (pintype "passive"))
    )
    (net (code "85") (name "unconnected-(SV2-Pad5)") (class "Default")
      (node (ref "SV2") (pin "5") (pinfunction "5_5") (pintype "passive"))
    )
    (net (code "86") (name "unconnected-(SV2-Pad7)") (class "Default")
      (node (ref "SV2") (pin "7") (pinfunction "7_7") (pintype "passive"))
    )
    (net (code "87") (name "unconnected-(SV2-Pad8)") (class "Default")
      (node (ref "SV2") (pin "8") (pinfunction "8_8") (pintype "passive"))
    )
    (net (code "88") (name "unconnected-(SV2-Pad10)") (class "Default")
      (node (ref "SV2") (pin "10") (pinfunction "10_10") (pintype "passive"))
    )
    (net (code "89") (name "unconnected-(SV2-Pad11)") (class "Default")
      (node (ref "SV2") (pin "11") (pinfunction "11_11") (pintype "passive"))
    )
    (net (code "90") (name "unconnected-(SV2-Pad12)") (class "Default")
      (node (ref "SV2") (pin "12") (pinfunction "12_12") (pintype "passive"))
    )
    (net (code "91") (name "unconnected-(SV2-Pad13)") (class "Default")
      (node (ref "SV2") (pin "13") (pinfunction "13_13") (pintype "passive"))
    )
    (net (code "92") (name "unconnected-(SV2-Pad14)") (class "Default")
      (node (ref "SV2") (pin "14") (pinfunction "14_14") (pintype "passive"))
    )
    (net (code "93") (name "unconnected-(SV2-Pad17)") (class "Default")
      (node (ref "SV2") (pin "17") (pinfunction "17_17") (pintype "passive"))
    )
    (net (code "94") (name "unconnected-(SV2-Pad19)") (class "Default")
      (node (ref "SV2") (pin "19") (pinfunction "19_19") (pintype "passive"))
    )
    (net (code "95") (name "unconnected-(SV2-Pad21)") (class "Default")
      (node (ref "SV2") (pin "21") (pinfunction "21_21") (pintype "passive"))
    )
    (net (code "96") (name "unconnected-(SV2-Pad22)") (class "Default")
      (node (ref "SV2") (pin "22") (pinfunction "22_22") (pintype "passive"))
    )
    (net (code "97") (name "unconnected-(SV2-Pad23)") (class "Default")
      (node (ref "SV2") (pin "23") (pinfunction "23_23") (pintype "passive"))
    )
    (net (code "98") (name "unconnected-(SV2-Pad24)") (class "Default")
      (node (ref "SV2") (pin "24") (pinfunction "24_24") (pintype "passive"))
    )
    (net (code "99") (name "unconnected-(SV2-Pad25)") (class "Default")
      (node (ref "SV2") (pin "25") (pinfunction "25_25") (pintype "passive"))
    )
    (net (code "100") (name "unconnected-(SV2-Pad26)") (class "Default")
      (node (ref "SV2") (pin "26") (pinfunction "26_26") (pintype "passive"))
    )
    (net (code "101") (name "unconnected-(SV2-Pad27)") (class "Default")
      (node (ref "SV2") (pin "27") (pinfunction "27_27") (pintype "passive"))
    )
    (net (code "102") (name "unconnected-(SV2-Pad28)") (class "Default")
      (node (ref "SV2") (pin "28") (pinfunction "28_28") (pintype "passive"))
    )
    (net (code "103") (name "unconnected-(SV2-Pad29)") (class "Default")
      (node (ref "SV2") (pin "29") (pinfunction "29_29") (pintype "passive"))
    )
    (net (code "104") (name "unconnected-(SV2-Pad31)") (class "Default")
      (node (ref "SV2") (pin "31") (pinfunction "31_31") (pintype "passive"))
    )
    (net (code "105") (name "unconnected-(SV2-Pad32)") (class "Default")
      (node (ref "SV2") (pin "32") (pinfunction "32_32") (pintype "passive"))
    )
    (net (code "106") (name "unconnected-(SV2-Pad33)") (class "Default")
      (node (ref "SV2") (pin "33") (pinfunction "33_33") (pintype "passive"))
    )
    (net (code "107") (name "unconnected-(SV2-Pad36)") (class "Default")
      (node (ref "SV2") (pin "36") (pinfunction "36_36") (pintype "passive"))
    )
    (net (code "108") (name "unconnected-(U$1-P0_COL-Pad18)") (class "Default")
      (node (ref "U$1") (pin "18") (pinfunction "P0_COL_18") (pintype "bidirectional"))
    )
    (net (code "109") (name "unconnected-(U$1-P0_CRS-Pad19)") (class "Default")
      (node (ref "U$1") (pin "19") (pinfunction "P0_CRS_19") (pintype "bidirectional"))
    )
    (net (code "110") (name "unconnected-(U$1-P0_INCLK-Pad8)") (class "Default")
      (node (ref "U$1") (pin "8") (pinfunction "P0_INCLK_8") (pintype "bidirectional"))
    )
    (net (code "111") (name "unconnected-(U$1-P0_IND2-Pad3)") (class "Default")
      (node (ref "U$1") (pin "3") (pinfunction "P0_IND2_3") (pintype "bidirectional"))
    )
    (net (code "112") (name "unconnected-(U$1-P0_IND3-Pad2)") (class "Default")
      (node (ref "U$1") (pin "2") (pinfunction "P0_IND3_2") (pintype "bidirectional"))
    )
    (net (code "113") (name "unconnected-(U$1-P0_INER-Pad7)") (class "Default")
      (node (ref "U$1") (pin "7") (pinfunction "P0_INER_7") (pintype "bidirectional"))
    )
  )
)
